# lm5175_smps_v0002.net
KiCad netlist of a schematic drawn in EAGLE
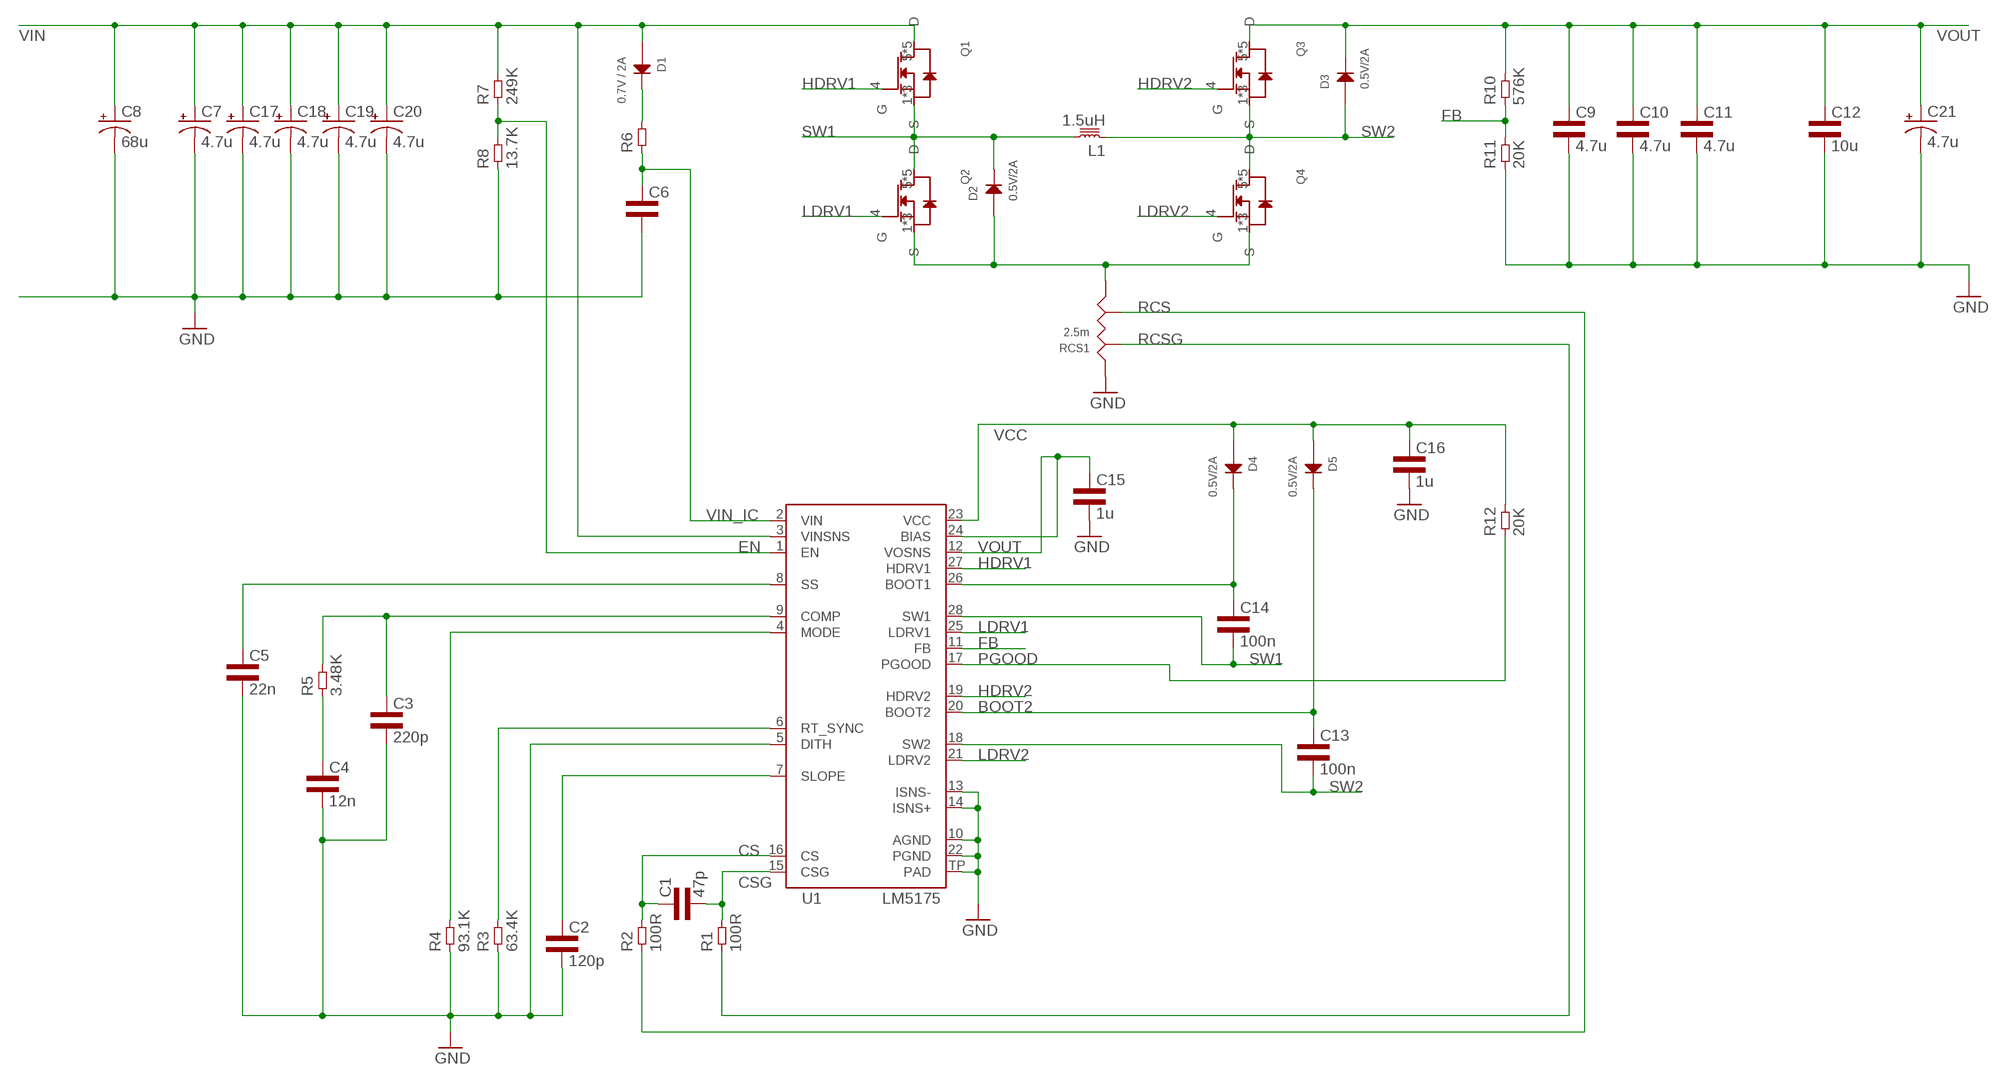
[diagram p0: schematic, sheet 1]

(export (version "E")
  (design (tool "Eeschema 10.0.6"))
  (components
    (comp (ref "C1")
      (value "47p")
      (footprint "eagle-import:0402L3")
      (libsource (lib "eagle-import") (part "CAP0402L3"))
    )
    (comp (ref "C2")
      (value "120p")
      (footprint "eagle-import:0603L3")
      (libsource (lib "eagle-import") (part "CAP0603L3"))
    )
    (comp (ref "C3")
      (value "220p")
      (footprint "eagle-import:0603L3")
      (libsource (lib "eagle-import") (part "CAP0603L3"))
    )
    (comp (ref "C4")
      (value "12n")
      (footprint "eagle-import:0603L3")
      (libsource (lib "eagle-import") (part "CAP0603L3"))
    )
    (comp (ref "C5")
      (value "22n")
      (footprint "eagle-import:0603L3")
      (libsource (lib "eagle-import") (part "CAP0603L3"))
    )
    (comp (ref "C6")
      (value "CAP0603L3")
      (footprint "eagle-import:0603L3")
      (libsource (lib "eagle-import") (part "CAP0603L3"))
    )
    (comp (ref "C7")
      (value "4.7u")
      (footprint "eagle-import:SANYO-OSCON_SMD_E12")
      (libsource (lib "eagle-import") (part "CPOL-USSANYO_SMD_E12"))
    )
    (comp (ref "C8")
      (value "68u")
      (footprint "eagle-import:153CLV-0810")
      (libsource (lib "eagle-import") (part "CPOL-US153CLV-0810"))
    )
    (comp (ref "C9")
      (value "4.7u")
      (footprint "eagle-import:1206L3")
      (libsource (lib "eagle-import") (part "CAP1206L3"))
    )
    (comp (ref "C10")
      (value "4.7u")
      (footprint "eagle-import:1206L3")
      (libsource (lib "eagle-import") (part "CAP1206L3"))
    )
    (comp (ref "C11")
      (value "4.7u")
      (footprint "eagle-import:1206L3")
      (libsource (lib "eagle-import") (part "CAP1206L3"))
    )
    (comp (ref "C12")
      (value "10u")
      (footprint "eagle-import:1206L3")
      (libsource (lib "eagle-import") (part "CAP1206L3"))
    )
    (comp (ref "C13")
      (value "100n")
      (footprint "eagle-import:0603L3")
      (libsource (lib "eagle-import") (part "CAP0603L3"))
    )
    (comp (ref "C14")
      (value "100n")
      (footprint "eagle-import:0603L3")
      (libsource (lib "eagle-import") (part "CAP0603L3"))
    )
    (comp (ref "C15")
      (value "1u")
      (footprint "eagle-import:0603L3")
      (libsource (lib "eagle-import") (part "CAP0603L3"))
    )
    (comp (ref "C16")
      (value "1u")
      (footprint "eagle-import:0603L3")
      (libsource (lib "eagle-import") (part "CAP0603L3"))
    )
    (comp (ref "C17")
      (value "4.7u")
      (footprint "eagle-import:SANYO-OSCON_SMD_E12")
      (libsource (lib "eagle-import") (part "CPOL-USSANYO_SMD_E12"))
    )
    (comp (ref "C18")
      (value "4.7u")
      (footprint "eagle-import:SANYO-OSCON_SMD_E12")
      (libsource (lib "eagle-import") (part "CPOL-USSANYO_SMD_E12"))
    )
    (comp (ref "C19")
      (value "4.7u")
      (footprint "eagle-import:SANYO-OSCON_SMD_E12")
      (libsource (lib "eagle-import") (part "CPOL-USSANYO_SMD_E12"))
    )
    (comp (ref "C20")
      (value "4.7u")
      (footprint "eagle-import:SANYO-OSCON_SMD_E12")
      (libsource (lib "eagle-import") (part "CPOL-USSANYO_SMD_E12"))
    )
    (comp (ref "C21")
      (value "4.7u")
      (footprint "eagle-import:SANYO-OSCON_SMD_E12")
      (libsource (lib "eagle-import") (part "CPOL-USSANYO_SMD_E12"))
    )
    (comp (ref "D1")
      (value "0.7V / 2A")
      (footprint "eagle-import:SMA-2")
      (libsource (lib "eagle-import") (part "DIODESMA"))
    )
    (comp (ref "D2")
      (value "0.5V/2A")
      (footprint "eagle-import:SMA-2")
      (libsource (lib "eagle-import") (part "DIODESMA"))
    )
    (comp (ref "D3")
      (value "0.5V/2A")
      (footprint "eagle-import:SMA-2")
      (libsource (lib "eagle-import") (part "DIODESMA"))
    )
    (comp (ref "D4")
      (value "0.5V/2A")
      (footprint "eagle-import:SMA-2")
      (libsource (lib "eagle-import") (part "DIODESMA"))
    )
    (comp (ref "D5")
      (value "0.5V/2A")
      (footprint "eagle-import:SMA-2")
      (libsource (lib "eagle-import") (part "DIODESMA"))
    )
    (comp (ref "L1")
      (value "1.5uH")
      (footprint "eagle-import:5.7X5.2")
      (libsource (lib "eagle-import") (part "INDUCTOR5752"))
    )
    (comp (ref "Q1")
      (value "CSD18540Q5B")
      (footprint "eagle-import:Q5B")
      (libsource (lib "eagle-import") (part "CSD18540Q5B"))
    )
    (comp (ref "Q2")
      (value "CSD18540Q5B")
      (footprint "eagle-import:Q5B")
      (libsource (lib "eagle-import") (part "CSD18540Q5B"))
    )
    (comp (ref "Q3")
      (value "CSD18540Q5B")
      (footprint "eagle-import:Q5B")
      (libsource (lib "eagle-import") (part "CSD18540Q5B"))
    )
    (comp (ref "Q4")
      (value "CSD18540Q5B")
      (footprint "eagle-import:Q5B")
      (libsource (lib "eagle-import") (part "CSD18540Q5B"))
    )
    (comp (ref "R1")
      (value "100R")
      (footprint "eagle-import:0603L3")
      (libsource (lib "eagle-import") (part "RES0603L3"))
    )
    (comp (ref "R2")
      (value "100R")
      (footprint "eagle-import:0603L3")
      (libsource (lib "eagle-import") (part "RES0603L3"))
    )
    (comp (ref "R3")
      (value "63.4K")
      (footprint "eagle-import:0603L3")
      (libsource (lib "eagle-import") (part "RES0603L3"))
    )
    (comp (ref "R4")
      (value "93.1K")
      (footprint "eagle-import:0603L3")
      (libsource (lib "eagle-import") (part "RES0603L3"))
    )
    (comp (ref "R5")
      (value "3.48K")
      (footprint "eagle-import:0603L3")
      (libsource (lib "eagle-import") (part "RES0603L3"))
    )
    (comp (ref "R6")
      (value "RES0603L3")
      (footprint "eagle-import:0603L3")
      (libsource (lib "eagle-import") (part "RES0603L3"))
    )
    (comp (ref "R7")
      (value "249K")
      (footprint "eagle-import:0603L3")
      (libsource (lib "eagle-import") (part "RES0603L3"))
    )
    (comp (ref "R8")
      (value "13.7K")
      (footprint "eagle-import:0603L3")
      (libsource (lib "eagle-import") (part "RES0603L3"))
    )
    (comp (ref "R10")
      (value "576K")
      (footprint "eagle-import:0603L3")
      (libsource (lib "eagle-import") (part "RES0603L3"))
    )
    (comp (ref "R11")
      (value "20K")
      (footprint "eagle-import:0603L3")
      (libsource (lib "eagle-import") (part "RES0603L3"))
    )
    (comp (ref "R12")
      (value "20K")
      (footprint "eagle-import:0603L3")
      (libsource (lib "eagle-import") (part "RES0603L3"))
    )
    (comp (ref "RCS1")
      (value "2.5m")
      (footprint "eagle-import:R2512")
      (libsource (lib "eagle-import") (part "CSRES"))
    )
    (comp (ref "U1")
      (value "LM5175")
      (footprint "eagle-import:R-PDSO-G28")
      (libsource (lib "eagle-import") (part "LM5175"))
    )
  )
  (nets
    (net (code "1") (name "/BOOT2") (class "Default")
      (node (ref "C13") (pin "P$1") (pinfunction "1_P$1") (pintype "bidirectional"))
      (node (ref "D5") (pin "2") (pinfunction "CATHODE_2") (pintype "bidirectional"))
      (node (ref "U1") (pin "20") (pinfunction "BOOT2_20") (pintype "bidirectional"))
    )
    (net (code "2") (name "/CS") (class "Default")
      (node (ref "C1") (pin "P$1") (pinfunction "1_P$1") (pintype "bidirectional"))
      (node (ref "R2") (pin "P$2") (pinfunction "2_P$2") (pintype "bidirectional"))
      (node (ref "U1") (pin "16") (pinfunction "CS_16") (pintype "bidirectional"))
    )
    (net (code "3") (name "/CSG") (class "Default")
      (node (ref "C1") (pin "P$2") (pinfunction "2_P$2") (pintype "bidirectional"))
      (node (ref "R1") (pin "P$2") (pinfunction "2_P$2") (pintype "bidirectional"))
      (node (ref "U1") (pin "15") (pinfunction "CSG_15") (pintype "bidirectional"))
    )
    (net (code "4") (name "/EN") (class "Default")
      (node (ref "R7") (pin "P$1") (pinfunction "1_P$1") (pintype "bidirectional"))
      (node (ref "R8") (pin "P$2") (pinfunction "2_P$2") (pintype "bidirectional"))
      (node (ref "U1") (pin "1") (pinfunction "EN_1") (pintype "bidirectional"))
    )
    (net (code "5") (name "/FB") (class "Default")
      (node (ref "R10") (pin "P$1") (pinfunction "1_P$1") (pintype "bidirectional"))
      (node (ref "R11") (pin "P$2") (pinfunction "2_P$2") (pintype "bidirectional"))
      (node (ref "U1") (pin "11") (pinfunction "FB_11") (pintype "bidirectional"))
    )
    (net (code "6") (name "/HDRV1") (class "Default")
      (node (ref "Q1") (pin "4") (pinfunction "G_4") (pintype "bidirectional"))
      (node (ref "U1") (pin "27") (pinfunction "HDRV1_27") (pintype "bidirectional"))
    )
    (net (code "7") (name "/HDRV2") (class "Default")
      (node (ref "Q3") (pin "4") (pinfunction "G_4") (pintype "bidirectional"))
      (node (ref "U1") (pin "19") (pinfunction "HDRV2_19") (pintype "bidirectional"))
    )
    (net (code "8") (name "/LDRV1") (class "Default")
      (node (ref "Q2") (pin "4") (pinfunction "G_4") (pintype "bidirectional"))
      (node (ref "U1") (pin "25") (pinfunction "LDRV1_25") (pintype "bidirectional"))
    )
    (net (code "9") (name "/LDRV2") (class "Default")
      (node (ref "Q4") (pin "4") (pinfunction "G_4") (pintype "bidirectional"))
      (node (ref "U1") (pin "21") (pinfunction "LDRV2_21") (pintype "bidirectional"))
    )
    (net (code "10") (name "/PGOOD") (class "Default")
      (node (ref "R12") (pin "P$1") (pinfunction "1_P$1") (pintype "bidirectional"))
      (node (ref "U1") (pin "17") (pinfunction "PGOOD_17") (pintype "bidirectional"))
    )
    (net (code "11") (name "/RCS") (class "Default")
      (node (ref "R2") (pin "P$1") (pinfunction "1_P$1") (pintype "bidirectional"))
      (node (ref "RCS1") (pin "CS_2") (pinfunction "CS_2_CS_2") (pintype "bidirectional"))
    )
    (net (code "12") (name "/RCSG") (class "Default")
      (node (ref "R1") (pin "P$1") (pinfunction "1_P$1") (pintype "bidirectional"))
      (node (ref "RCS1") (pin "CS_1") (pinfunction "CS_1_CS_1") (pintype "bidirectional"))
    )
    (net (code "13") (name "/SW1") (class "Default")
      (node (ref "C14") (pin "P$2") (pinfunction "2_P$2") (pintype "bidirectional"))
      (node (ref "D2") (pin "2") (pinfunction "CATHODE_2") (pintype "bidirectional"))
      (node (ref "L1") (pin "2") (pinfunction "2_2") (pintype "bidirectional"))
      (node (ref "Q1") (pin "1") (pinfunction "S_1") (pintype "bidirectional"))
      (node (ref "Q1") (pin "2") (pinfunction "S_2") (pintype "bidirectional"))
      (node (ref "Q1") (pin "3") (pinfunction "S_3") (pintype "bidirectional"))
      (node (ref "Q2") (pin "5") (pinfunction "D_5") (pintype "bidirectional"))
      (node (ref "Q2") (pin "6") (pinfunction "D_6") (pintype "bidirectional"))
      (node (ref "Q2") (pin "7") (pinfunction "D_7") (pintype "bidirectional"))
      (node (ref "Q2") (pin "8") (pinfunction "D_8") (pintype "bidirectional"))
      (node (ref "Q2") (pin "9") (pinfunction "D_9") (pintype "bidirectional"))
      (node (ref "U1") (pin "28") (pinfunction "SW1_28") (pintype "bidirectional"))
    )
    (net (code "14") (name "/SW2") (class "Default")
      (node (ref "C13") (pin "P$2") (pinfunction "2_P$2") (pintype "bidirectional"))
      (node (ref "D3") (pin "1") (pinfunction "ANODE_1") (pintype "bidirectional"))
      (node (ref "L1") (pin "1") (pinfunction "1_1") (pintype "bidirectional"))
      (node (ref "Q3") (pin "1") (pinfunction "S_1") (pintype "bidirectional"))
      (node (ref "Q3") (pin "2") (pinfunction "S_2") (pintype "bidirectional"))
      (node (ref "Q3") (pin "3") (pinfunction "S_3") (pintype "bidirectional"))
      (node (ref "Q4") (pin "5") (pinfunction "D_5") (pintype "bidirectional"))
      (node (ref "Q4") (pin "6") (pinfunction "D_6") (pintype "bidirectional"))
      (node (ref "Q4") (pin "7") (pinfunction "D_7") (pintype "bidirectional"))
      (node (ref "Q4") (pin "8") (pinfunction "D_8") (pintype "bidirectional"))
      (node (ref "Q4") (pin "9") (pinfunction "D_9") (pintype "bidirectional"))
      (node (ref "U1") (pin "18") (pinfunction "SW2_18") (pintype "bidirectional"))
    )
    (net (code "15") (name "/VCC") (class "Default")
      (node (ref "C16") (pin "P$1") (pinfunction "1_P$1") (pintype "bidirectional"))
      (node (ref "D4") (pin "1") (pinfunction "ANODE_1") (pintype "bidirectional"))
      (node (ref "D5") (pin "1") (pinfunction "ANODE_1") (pintype "bidirectional"))
      (node (ref "R12") (pin "P$2") (pinfunction "2_P$2") (pintype "bidirectional"))
      (node (ref "U1") (pin "23") (pinfunction "VCC_23") (pintype "bidirectional"))
    )
    (net (code "16") (name "/VIN") (class "Default")
      (node (ref "C17") (pin "+") (pinfunction "+_+") (pintype "passive"))
      (node (ref "C18") (pin "+") (pinfunction "+_+") (pintype "passive"))
      (node (ref "C19") (pin "+") (pinfunction "+_+") (pintype "passive"))
      (node (ref "C20") (pin "+") (pinfunction "+_+") (pintype "passive"))
      (node (ref "C7") (pin "+") (pinfunction "+_+") (pintype "passive"))
      (node (ref "C8") (pin "+") (pinfunction "+_+") (pintype "passive"))
      (node (ref "D1") (pin "1") (pinfunction "ANODE_1") (pintype "bidirectional"))
      (node (ref "Q1") (pin "5") (pinfunction "D_5") (pintype "bidirectional"))
      (node (ref "Q1") (pin "6") (pinfunction "D_6") (pintype "bidirectional"))
      (node (ref "Q1") (pin "7") (pinfunction "D_7") (pintype "bidirectional"))
      (node (ref "Q1") (pin "8") (pinfunction "D_8") (pintype "bidirectional"))
      (node (ref "Q1") (pin "9") (pinfunction "D_9") (pintype "bidirectional"))
      (node (ref "R7") (pin "P$2") (pinfunction "2_P$2") (pintype "bidirectional"))
      (node (ref "U1") (pin "3") (pinfunction "VINSNS_3") (pintype "bidirectional"))
    )
    (net (code "17") (name "/VIN_IC") (class "Default")
      (node (ref "C6") (pin "P$1") (pinfunction "1_P$1") (pintype "bidirectional"))
      (node (ref "R6") (pin "P$1") (pinfunction "1_P$1") (pintype "bidirectional"))
      (node (ref "U1") (pin "2") (pinfunction "VIN_2") (pintype "bidirectional"))
    )
    (net (code "18") (name "/VOUT") (class "Default")
      (node (ref "C10") (pin "1") (pinfunction "1_1") (pintype "bidirectional"))
      (node (ref "C11") (pin "1") (pinfunction "1_1") (pintype "bidirectional"))
      (node (ref "C12") (pin "1") (pinfunction "1_1") (pintype "bidirectional"))
      (node (ref "C15") (pin "P$1") (pinfunction "1_P$1") (pintype "bidirectional"))
      (node (ref "C21") (pin "+") (pinfunction "+_+") (pintype "passive"))
      (node (ref "C9") (pin "1") (pinfunction "1_1") (pintype "bidirectional"))
      (node (ref "D3") (pin "2") (pinfunction "CATHODE_2") (pintype "bidirectional"))
      (node (ref "Q3") (pin "5") (pinfunction "D_5") (pintype "bidirectional"))
      (node (ref "Q3") (pin "6") (pinfunction "D_6") (pintype "bidirectional"))
      (node (ref "Q3") (pin "7") (pinfunction "D_7") (pintype "bidirectional"))
      (node (ref "Q3") (pin "8") (pinfunction "D_8") (pintype "bidirectional"))
      (node (ref "Q3") (pin "9") (pinfunction "D_9") (pintype "bidirectional"))
      (node (ref "R10") (pin "P$2") (pinfunction "2_P$2") (pintype "bidirectional"))
      (node (ref "U1") (pin "12") (pinfunction "VOSNS_12") (pintype "bidirectional"))
      (node (ref "U1") (pin "24") (pinfunction "BIAS_24") (pintype "bidirectional"))
    )
    (net (code "19") (name "GND") (class "Default")
      (node (ref "C10") (pin "2") (pinfunction "2_2") (pintype "bidirectional"))
      (node (ref "C11") (pin "2") (pinfunction "2_2") (pintype "bidirectional"))
      (node (ref "C12") (pin "2") (pinfunction "2_2") (pintype "bidirectional"))
      (node (ref "C15") (pin "P$2") (pinfunction "2_P$2") (pintype "bidirectional"))
      (node (ref "C16") (pin "P$2") (pinfunction "2_P$2") (pintype "bidirectional"))
      (node (ref "C17") (pin "-") (pinfunction "-_-") (pintype "passive"))
      (node (ref "C18") (pin "-") (pinfunction "-_-") (pintype "passive"))
      (node (ref "C19") (pin "-") (pinfunction "-_-") (pintype "passive"))
      (node (ref "C2") (pin "P$2") (pinfunction "2_P$2") (pintype "bidirectional"))
      (node (ref "C20") (pin "-") (pinfunction "-_-") (pintype "passive"))
      (node (ref "C21") (pin "-") (pinfunction "-_-") (pintype "passive"))
      (node (ref "C3") (pin "P$2") (pinfunction "2_P$2") (pintype "bidirectional"))
      (node (ref "C4") (pin "P$2") (pinfunction "2_P$2") (pintype "bidirectional"))
      (node (ref "C5") (pin "P$2") (pinfunction "2_P$2") (pintype "bidirectional"))
      (node (ref "C6") (pin "P$2") (pinfunction "2_P$2") (pintype "bidirectional"))
      (node (ref "C7") (pin "-") (pinfunction "-_-") (pintype "passive"))
      (node (ref "C8") (pin "-") (pinfunction "-_-") (pintype "passive"))
      (node (ref "C9") (pin "2") (pinfunction "2_2") (pintype "bidirectional"))
      (node (ref "R11") (pin "P$1") (pinfunction "1_P$1") (pintype "bidirectional"))
      (node (ref "R3") (pin "P$1") (pinfunction "1_P$1") (pintype "bidirectional"))
      (node (ref "R4") (pin "P$1") (pinfunction "1_P$1") (pintype "bidirectional"))
      (node (ref "R8") (pin "P$1") (pinfunction "1_P$1") (pintype "bidirectional"))
      (node (ref "RCS1") (pin "1_1") (pinfunction "1_1_1") (pintype "bidirectional"))
      (node (ref "RCS1") (pin "1_2") (pinfunction "1_1_2") (pintype "bidirectional"))
      (node (ref "U1") (pin "10") (pinfunction "AGND_10") (pintype "bidirectional"))
      (node (ref "U1") (pin "13") (pinfunction "ISNS-_13") (pintype "bidirectional"))
      (node (ref "U1") (pin "14") (pinfunction "ISNS+_14") (pintype "bidirectional"))
      (node (ref "U1") (pin "22") (pinfunction "PGND_22") (pintype "bidirectional"))
      (node (ref "U1") (pin "5") (pinfunction "DITH_5") (pintype "bidirectional"))
      (node (ref "U1") (pin "TP") (pinfunction "PAD_TP") (pintype "bidirectional"))
    )
    (net (code "20") (name "Net-(C2-1)") (class "Default")
      (node (ref "C2") (pin "P$1") (pinfunction "1_P$1") (pintype "bidirectional"))
      (node (ref "U1") (pin "7") (pinfunction "SLOPE_7") (pintype "bidirectional"))
    )
    (net (code "21") (name "Net-(C3-1)") (class "Default")
      (node (ref "C3") (pin "P$1") (pinfunction "1_P$1") (pintype "bidirectional"))
      (node (ref "R5") (pin "P$2") (pinfunction "2_P$2") (pintype "bidirectional"))
      (node (ref "U1") (pin "9") (pinfunction "COMP_9") (pintype "bidirectional"))
    )
    (net (code "22") (name "Net-(C4-1)") (class "Default")
      (node (ref "C4") (pin "P$1") (pinfunction "1_P$1") (pintype "bidirectional"))
      (node (ref "R5") (pin "P$1") (pinfunction "1_P$1") (pintype "bidirectional"))
    )
    (net (code "23") (name "Net-(C5-1)") (class "Default")
      (node (ref "C5") (pin "P$1") (pinfunction "1_P$1") (pintype "bidirectional"))
      (node (ref "U1") (pin "8") (pinfunction "SS_8") (pintype "bidirectional"))
    )
    (net (code "24") (name "Net-(C14-1)") (class "Default")
      (node (ref "C14") (pin "P$1") (pinfunction "1_P$1") (pintype "bidirectional"))
      (node (ref "D4") (pin "2") (pinfunction "CATHODE_2") (pintype "bidirectional"))
      (node (ref "U1") (pin "26") (pinfunction "BOOT1_26") (pintype "bidirectional"))
    )
    (net (code "25") (name "Net-(D1-CATHODE)") (class "Default")
      (node (ref "D1") (pin "2") (pinfunction "CATHODE_2") (pintype "bidirectional"))
      (node (ref "R6") (pin "P$2") (pinfunction "2_P$2") (pintype "bidirectional"))
    )
    (net (code "26") (name "Net-(D2-ANODE)") (class "Default")
      (node (ref "D2") (pin "1") (pinfunction "ANODE_1") (pintype "bidirectional"))
      (node (ref "Q2") (pin "1") (pinfunction "S_1") (pintype "bidirectional"))
      (node (ref "Q2") (pin "2") (pinfunction "S_2") (pintype "bidirectional"))
      (node (ref "Q2") (pin "3") (pinfunction "S_3") (pintype "bidirectional"))
      (node (ref "Q4") (pin "1") (pinfunction "S_1") (pintype "bidirectional"))
      (node (ref "Q4") (pin "2") (pinfunction "S_2") (pintype "bidirectional"))
      (node (ref "Q4") (pin "3") (pinfunction "S_3") (pintype "bidirectional"))
      (node (ref "RCS1") (pin "2_1") (pinfunction "2_2_1") (pintype "bidirectional"))
      (node (ref "RCS1") (pin "2_2") (pinfunction "2_2_2") (pintype "bidirectional"))
    )
    (net (code "27") (name "Net-(R3-2)") (class "Default")
      (node (ref "R3") (pin "P$2") (pinfunction "2_P$2") (pintype "bidirectional"))
      (node (ref "U1") (pin "6") (pinfunction "RT_SYNC_6") (pintype "bidirectional"))
    )
    (net (code "28") (name "Net-(R4-2)") (class "Default")
      (node (ref "R4") (pin "P$2") (pinfunction "2_P$2") (pintype "bidirectional"))
      (node (ref "U1") (pin "4") (pinfunction "MODE_4") (pintype "bidirectional"))
    )
  )
)
